# CON_PS2KEYBOARD_MINIDIN6F.net
KiCad netlist of a schematic drawn in Altium Designer
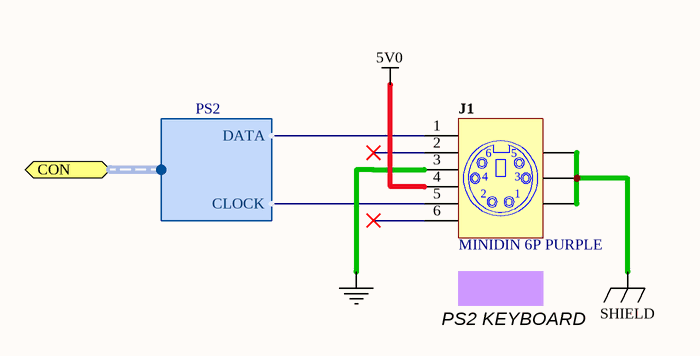
[diagram p0: CON_PS2KEYBOARD_MINIDIN6F.SchDoc]

(export (version "E")
  (design (tool "Eeschema 10.0.6"))
  (components
    (comp (ref "J1")
      (value "MINIDIN 6P PURPLE")
      (footprint "MINIDIN6PURPLE")
      (description "MINI DIN R/A F/SHLD 6P GOLD PLATED--PURPLE PC99 RoHS Compliant")
      (libsource (lib "AltiumDesignLibrary") (part "CON-MINIDIN-6-F"))
    )
  )
  (nets
    (net (code "2") (name "/CLOCK") (class "Default")
      (node (ref "J1") (pin "5") (pinfunction "5_5") (pintype "passive"))
    )
    (net (code "3") (name "/DATA") (class "Default")
      (node (ref "J1") (pin "1") (pinfunction "1_1") (pintype "passive"))
    )
    (net (code "5") (name "5V0") (class "Default")
      (node (ref "J1") (pin "4") (pinfunction "4_4") (pintype "passive"))
    )
    (net (code "6") (name "GND") (class "Default")
      (node (ref "J1") (pin "3") (pinfunction "3_3") (pintype "passive"))
    )
    (net (code "7") (name "SHIELD") (class "Default")
      (node (ref "J1") (pin "MH1") (pinfunction "MH1_MH1") (pintype "passive"))
      (node (ref "J1") (pin "MH2") (pinfunction "MH2_MH2") (pintype "passive"))
      (node (ref "J1") (pin "MH3") (pinfunction "MH3_MH3") (pintype "passive"))
    )
    (net (code "8") (name "unconnected-(J1-Pad2)") (class "Default")
      (node (ref "J1") (pin "2") (pinfunction "2_2") (pintype "passive+no_connect"))
    )
    (net (code "9") (name "unconnected-(J1-Pad6)") (class "Default")
      (node (ref "J1") (pin "6") (pinfunction "6_6") (pintype "passive+no_connect"))
    )
  )
)
